# Sheet1.net
KiCad netlist of a schematic drawn in Altium Designer
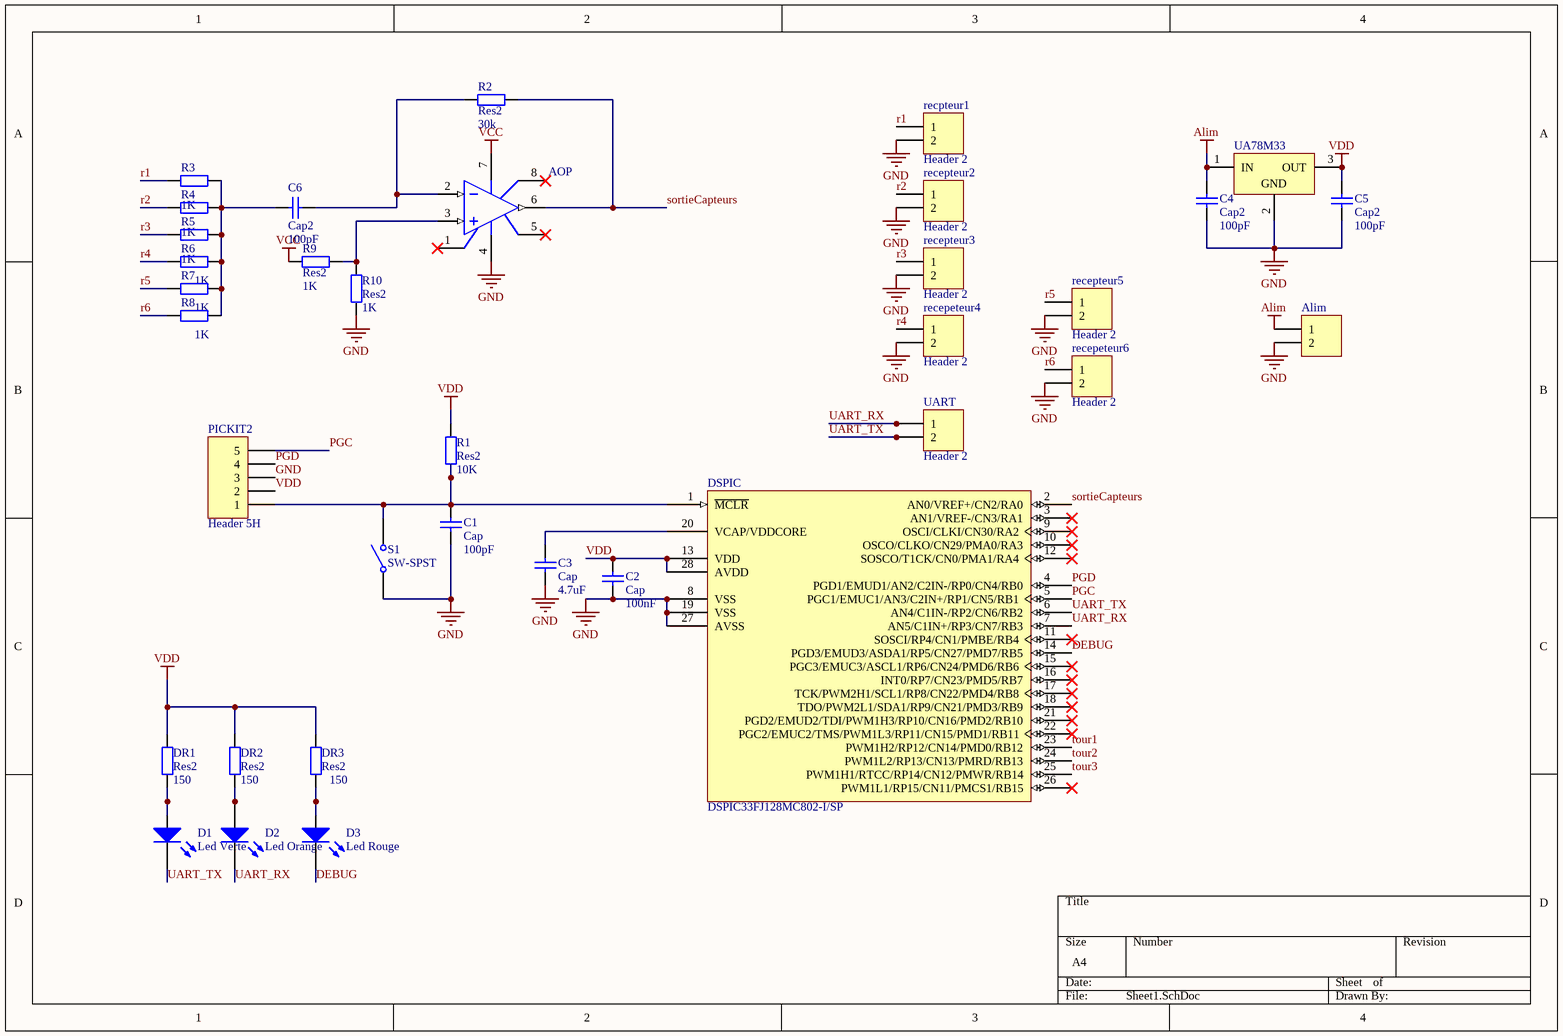
[diagram p0: Sheet1.SchDoc]

(export (version "E")
  (design (tool "Eeschema 10.0.6"))
  (components
    (comp (ref "Alim")
      (value "Header 2")
      (footprint "HDR1X2")
      (description "Header, 2-Pin")
      (fields (field (name "PUBLISHER") "Altium Limited"))
      (libsource (lib "Miscellaneous Connectors") (part "Header 2"))
    )
    (comp (ref "AOP")
      (value "TL081CN")
      (footprint "DIP8")
      (description "General-Purpose J-FET Single Operational Amplifier")
      (fields (field (name "PUBLISHER") "Altium Limited"))
      (libsource (lib "LIBRAIRIE_INTEGREE_PHELMA1") (part "TL081CN"))
    )
    (comp (ref "C1")
      (value "Cap")
      (footprint "RAD-0.3")
      (description "Capacitor")
      (fields (field (name "ALTIUM_VALUE") "100pF") (field (name "PUBLISHER") "Altium Limited"))
      (libsource (lib "Miscellaneous Devices") (part "Cap"))
    )
    (comp (ref "C2")
      (value "Cap")
      (footprint "RAD-0.3")
      (description "Capacitor")
      (fields (field (name "ALTIUM_VALUE") "100nF") (field (name "PUBLISHER") "Altium Limited"))
      (libsource (lib "Miscellaneous Devices") (part "Cap"))
    )
    (comp (ref "C3")
      (value "Cap")
      (footprint "RAD-0.3")
      (description "Capacitor")
      (fields (field (name "ALTIUM_VALUE") "4.7uF") (field (name "PUBLISHER") "Altium Limited"))
      (libsource (lib "Miscellaneous Devices") (part "Cap"))
    )
    (comp (ref "C4")
      (value "Cap2")
      (footprint "CAPA2")
      (description "Capacitor")
      (fields (field (name "ALTIUM_VALUE") "100pF") (field (name "PUBLISHER") "Altium Limited"))
      (libsource (lib "LIBRAIRIE_INTEGREE_PHELMA1") (part "Cap2"))
    )
    (comp (ref "C5")
      (value "Cap2")
      (footprint "CAPA2")
      (description "Capacitor")
      (fields (field (name "ALTIUM_VALUE") "100pF") (field (name "PUBLISHER") "Altium Limited"))
      (libsource (lib "LIBRAIRIE_INTEGREE_PHELMA1") (part "Cap2"))
    )
    (comp (ref "C6")
      (value "Cap2")
      (footprint "CAPA2")
      (description "Capacitor")
      (fields (field (name "ALTIUM_VALUE") "100pF") (field (name "PUBLISHER") "Altium Limited"))
      (libsource (lib "LIBRAIRIE_INTEGREE_PHELMA1") (part "Cap2"))
    )
    (comp (ref "D1")
      (value "Led Verte")
      (footprint "LED")
      (description "LED")
      (fields (field (name "PUBLISHER") "Altium Limited"))
      (libsource (lib "LIBRAIRIE_INTEGREE_PHELMA1") (part "Led"))
    )
    (comp (ref "D2")
      (value "Led Orange")
      (footprint "LED")
      (description "LED")
      (fields (field (name "PUBLISHER") "Altium Limited"))
      (libsource (lib "LIBRAIRIE_INTEGREE_PHELMA1") (part "Led"))
    )
    (comp (ref "D3")
      (value "Led Rouge")
      (footprint "LED")
      (description "LED")
      (fields (field (name "PUBLISHER") "Altium Limited"))
      (libsource (lib "LIBRAIRIE_INTEGREE_PHELMA1") (part "Led"))
    )
    (comp (ref "DR1")
      (value "Res2")
      (footprint "AXIAL-0.4")
      (description "Resistor")
      (fields (field (name "ALTIUM_VALUE") "150") (field (name "PUBLISHER") "Altium Limited"))
      (libsource (lib "Miscellaneous Devices") (part "Res2"))
    )
    (comp (ref "DR2")
      (value "Res2")
      (footprint "AXIAL-0.4")
      (description "Resistor")
      (fields (field (name "ALTIUM_VALUE") "150") (field (name "PUBLISHER") "Altium Limited"))
      (libsource (lib "Miscellaneous Devices") (part "Res2"))
    )
    (comp (ref "DR3")
      (value "Res2")
      (footprint "AXIAL-0.4")
      (description "Resistor")
      (fields (field (name "ALTIUM_VALUE") "150") (field (name "PUBLISHER") "Altium Limited"))
      (libsource (lib "Miscellaneous Devices") (part "Res2"))
    )
    (comp (ref "DSPIC")
      (value "DSPIC33FJ128MC802-I/SP")
      (footprint "SPDIP300-SP28")
      (fields (field (name "PUBLISHER") "Altium Limited"))
      (libsource (lib "Microchip DSC 16-Bit dsPIC33F") (part "DSPIC33FJ128MC802-I/SP"))
    )
    (comp (ref "PICKIT2")
      (value "Header 5H")
      (footprint "HDR1X5")
      (description "Header, 5-Pin, Right Angle")
      (fields (field (name "PUBLISHER") "Altium Limited"))
      (libsource (lib "Miscellaneous Connectors") (part "Header 5H"))
    )
    (comp (ref "R1")
      (value "Res2")
      (footprint "AXIAL-0.4")
      (description "Resistor")
      (fields (field (name "ALTIUM_VALUE") "10K") (field (name "PUBLISHER") "Altium Limited"))
      (libsource (lib "Miscellaneous Devices") (part "Res2"))
    )
    (comp (ref "R2")
      (value "Res2")
      (footprint "res5_1/4W")
      (description "Resistor")
      (fields (field (name "ALTIUM_VALUE") "30k") (field (name "PUBLISHER") "Altium Limited"))
      (libsource (lib "LIBRAIRIE_INTEGREE_PHELMA1") (part "Res2"))
    )
    (comp (ref "R3")
      (value "1K")
      (footprint "res5_1/4W")
      (description "Resistor")
      (fields (field (name "Comment") "Res2") (field (name "PUBLISHER") "Altium Limited"))
      (libsource (lib "LIBRAIRIE_INTEGREE_PHELMA1") (part "Res2"))
    )
    (comp (ref "R4")
      (value "1K")
      (footprint "res5_1/4W")
      (description "Resistor")
      (fields (field (name "Comment") "Res2") (field (name "PUBLISHER") "Altium Limited"))
      (libsource (lib "LIBRAIRIE_INTEGREE_PHELMA1") (part "Res2"))
    )
    (comp (ref "R5")
      (value "1K")
      (footprint "res5_1/4W")
      (description "Resistor")
      (fields (field (name "Comment") "Res2") (field (name "PUBLISHER") "Altium Limited"))
      (libsource (lib "LIBRAIRIE_INTEGREE_PHELMA1") (part "Res2"))
    )
    (comp (ref "R6")
      (value "1K")
      (footprint "res5_1/4W")
      (description "Resistor")
      (fields (field (name "Comment") "Res2") (field (name "PUBLISHER") "Altium Limited"))
      (libsource (lib "LIBRAIRIE_INTEGREE_PHELMA1") (part "Res2"))
    )
    (comp (ref "R7")
      (value "1K")
      (footprint "res5_1/4W")
      (description "Resistor")
      (fields (field (name "Comment") "Res2") (field (name "PUBLISHER") "Altium Limited"))
      (libsource (lib "LIBRAIRIE_INTEGREE_PHELMA1") (part "Res2"))
    )
    (comp (ref "R8")
      (value "1K")
      (footprint "res5_1/4W")
      (description "Resistor")
      (fields (field (name "Comment") "Res2") (field (name "PUBLISHER") "Altium Limited"))
      (libsource (lib "LIBRAIRIE_INTEGREE_PHELMA1") (part "Res2"))
    )
    (comp (ref "R9")
      (value "Res2")
      (footprint "res5_1/4W")
      (description "Resistor")
      (fields (field (name "ALTIUM_VALUE") "1K") (field (name "PUBLISHER") "Altium Limited"))
      (libsource (lib "LIBRAIRIE_INTEGREE_PHELMA1") (part "Res2"))
    )
    (comp (ref "R10")
      (value "Res2")
      (footprint "res5_1/4W")
      (description "Resistor")
      (fields (field (name "ALTIUM_VALUE") "1K") (field (name "PUBLISHER") "Altium Limited"))
      (libsource (lib "") (part "Res2_1"))
    )
    (comp (ref "recepeteur4")
      (value "Header 2")
      (footprint "HDR1X2")
      (description "Header, 2-Pin")
      (fields (field (name "PUBLISHER") "Altium Limited"))
      (libsource (lib "Miscellaneous Connectors") (part "Header 2"))
    )
    (comp (ref "recepeteur6")
      (value "Header 2")
      (footprint "HDR1X2")
      (description "Header, 2-Pin")
      (fields (field (name "PUBLISHER") "Altium Limited"))
      (libsource (lib "Miscellaneous Connectors") (part "Header 2"))
    )
    (comp (ref "recepteur2")
      (value "Header 2")
      (footprint "HDR1X2")
      (description "Header, 2-Pin")
      (fields (field (name "PUBLISHER") "Altium Limited"))
      (libsource (lib "Miscellaneous Connectors") (part "Header 2"))
    )
    (comp (ref "recepteur3")
      (value "Header 2")
      (footprint "HDR1X2")
      (description "Header, 2-Pin")
      (fields (field (name "PUBLISHER") "Altium Limited"))
      (libsource (lib "Miscellaneous Connectors") (part "Header 2"))
    )
    (comp (ref "recepteur5")
      (value "Header 2")
      (footprint "HDR1X2")
      (description "Header, 2-Pin")
      (fields (field (name "PUBLISHER") "Altium Limited"))
      (libsource (lib "Miscellaneous Connectors") (part "Header 2"))
    )
    (comp (ref "recpteur1")
      (value "Header 2")
      (footprint "HDR1X2")
      (description "Header, 2-Pin")
      (fields (field (name "PUBLISHER") "Altium Limited"))
      (libsource (lib "Miscellaneous Connectors") (part "Header 2"))
    )
    (comp (ref "S1")
      (value "SW-SPST")
      (footprint "SPST-2")
      (description "Single-Pole, Single-Throw Switch")
      (fields (field (name "PUBLISHER") "Altium Limited"))
      (libsource (lib "Miscellaneous Devices") (part "SW-SPST"))
    )
    (comp (ref "UA78M33")
      (value "LM7805CT")
      (footprint "TO220")
      (description "Series 3-Terminal Positive Regulator")
      (fields (field (name "PUBLISHER") "Altium Limited"))
      (libsource (lib "LIBRAIRIE_INTEGREE_PHELMA1") (part "LM7805CT"))
    )
    (comp (ref "UART")
      (value "Header 2")
      (footprint "HDR1X2")
      (description "Header, 2-Pin")
      (fields (field (name "PUBLISHER") "Altium Limited"))
      (libsource (lib "Miscellaneous Connectors") (part "Header 2"))
    )
  )
  (nets
    (net (code "1") (name "/DEBUG") (class "Default")
      (node (ref "D3") (pin "2") (pinfunction "K_2") (pintype "passive"))
      (node (ref "DSPIC") (pin "14") (pinfunction "PGD3/EMUD3/ASDA1/RP5/CN27/PMD7/RB5_14") (pintype "bidirectional"))
    )
    (net (code "2") (name "/PGC") (class "Default")
      (node (ref "DSPIC") (pin "5") (pinfunction "PGC1/EMUC1/AN3/C2IN+/RP1/CN5/RB1_5") (pintype "bidirectional"))
      (node (ref "PICKIT2") (pin "5") (pinfunction "5_5") (pintype "passive"))
    )
    (net (code "3") (name "/PGD") (class "Default")
      (node (ref "DSPIC") (pin "4") (pinfunction "PGD1/EMUD1/AN2/C2IN-/RP0/CN4/RB0_4") (pintype "bidirectional"))
      (node (ref "PICKIT2") (pin "4") (pinfunction "4_4") (pintype "passive"))
    )
    (net (code "4") (name "/UART_RX") (class "Default")
      (node (ref "D2") (pin "2") (pinfunction "K_2") (pintype "passive"))
      (node (ref "DSPIC") (pin "7") (pinfunction "AN5/C1IN+/RP3/CN7/RB3_7") (pintype "bidirectional"))
      (node (ref "UART") (pin "1") (pinfunction "1_1") (pintype "passive"))
    )
    (net (code "5") (name "/UART_TX") (class "Default")
      (node (ref "D1") (pin "2") (pinfunction "K_2") (pintype "passive"))
      (node (ref "DSPIC") (pin "6") (pinfunction "AN4/C1IN-/RP2/CN6/RB2_6") (pintype "bidirectional"))
      (node (ref "UART") (pin "2") (pinfunction "2_2") (pintype "passive"))
    )
    (net (code "6") (name "/r1") (class "Default")
      (node (ref "R3") (pin "1") (pinfunction "1_1") (pintype "passive"))
      (node (ref "recpteur1") (pin "1") (pinfunction "1_1") (pintype "passive"))
    )
    (net (code "7") (name "/r2") (class "Default")
      (node (ref "R4") (pin "1") (pinfunction "1_1") (pintype "passive"))
      (node (ref "recepteur2") (pin "1") (pinfunction "1_1") (pintype "passive"))
    )
    (net (code "8") (name "/r3") (class "Default")
      (node (ref "R5") (pin "1") (pinfunction "1_1") (pintype "passive"))
      (node (ref "recepteur3") (pin "1") (pinfunction "1_1") (pintype "passive"))
    )
    (net (code "9") (name "/r4") (class "Default")
      (node (ref "R6") (pin "1") (pinfunction "1_1") (pintype "passive"))
      (node (ref "recepeteur4") (pin "1") (pinfunction "1_1") (pintype "passive"))
    )
    (net (code "10") (name "/r5") (class "Default")
      (node (ref "R7") (pin "1") (pinfunction "1_1") (pintype "passive"))
      (node (ref "recepteur5") (pin "1") (pinfunction "1_1") (pintype "passive"))
    )
    (net (code "11") (name "/r6") (class "Default")
      (node (ref "R8") (pin "1") (pinfunction "1_1") (pintype "passive"))
      (node (ref "recepeteur6") (pin "1") (pinfunction "1_1") (pintype "passive"))
    )
    (net (code "12") (name "/sortieCapteurs") (class "Default")
      (node (ref "AOP") (pin "6") (pinfunction "OUT_6") (pintype "output"))
      (node (ref "DSPIC") (pin "2") (pinfunction "AN0/VREF+/CN2/RA0_2") (pintype "bidirectional"))
      (node (ref "R2") (pin "2") (pinfunction "2_2") (pintype "passive"))
    )
    (net (code "13") (name "/tour1") (class "Default")
      (node (ref "DSPIC") (pin "23") (pinfunction "PWM1H2/RP12/CN14/PMD0/RB12_23") (pintype "bidirectional"))
    )
    (net (code "14") (name "/tour2") (class "Default")
      (node (ref "DSPIC") (pin "24") (pinfunction "PWM1L2/RP13/CN13/PMRD/RB13_24") (pintype "bidirectional"))
    )
    (net (code "15") (name "/tour3") (class "Default")
      (node (ref "DSPIC") (pin "25") (pinfunction "PWM1H1/RTCC/RP14/CN12/PMWR/RB14_25") (pintype "bidirectional"))
    )
    (net (code "16") (name "Alim") (class "Default")
      (node (ref "Alim") (pin "1") (pinfunction "1_1") (pintype "passive"))
      (node (ref "C4") (pin "2") (pinfunction "2_2") (pintype "passive"))
      (node (ref "UA78M33") (pin "1") (pinfunction "IN_1") (pintype "power_in"))
    )
    (net (code "17") (name "GND") (class "Default")
      (node (ref "AOP") (pin "4") (pinfunction "V-_4") (pintype "power_in"))
      (node (ref "Alim") (pin "2") (pinfunction "2_2") (pintype "passive"))
      (node (ref "C1") (pin "1") (pinfunction "1_1") (pintype "passive"))
      (node (ref "C2") (pin "1") (pinfunction "1_1") (pintype "passive"))
      (node (ref "C3") (pin "1") (pinfunction "1_1") (pintype "passive"))
      (node (ref "C4") (pin "1") (pinfunction "1_1") (pintype "passive"))
      (node (ref "C5") (pin "1") (pinfunction "1_1") (pintype "passive"))
      (node (ref "DSPIC") (pin "19") (pinfunction "VSS_19") (pintype "power_in"))
      (node (ref "DSPIC") (pin "27") (pinfunction "AVSS_27") (pintype "power_in"))
      (node (ref "DSPIC") (pin "8") (pinfunction "VSS_8") (pintype "power_in"))
      (node (ref "PICKIT2") (pin "3") (pinfunction "3_3") (pintype "passive"))
      (node (ref "R10") (pin "1") (pinfunction "1_1") (pintype "passive"))
      (node (ref "S1") (pin "1") (pinfunction "COMMON_1") (pintype "passive"))
      (node (ref "UA78M33") (pin "2") (pinfunction "GND_2") (pintype "power_in"))
      (node (ref "recepeteur4") (pin "2") (pinfunction "2_2") (pintype "passive"))
      (node (ref "recepeteur6") (pin "2") (pinfunction "2_2") (pintype "passive"))
      (node (ref "recepteur2") (pin "2") (pinfunction "2_2") (pintype "passive"))
      (node (ref "recepteur3") (pin "2") (pinfunction "2_2") (pintype "passive"))
      (node (ref "recepteur5") (pin "2") (pinfunction "2_2") (pintype "passive"))
      (node (ref "recpteur1") (pin "2") (pinfunction "2_2") (pintype "passive"))
    )
    (net (code "18") (name "Net-(AOP-IN+)") (class "Default")
      (node (ref "AOP") (pin "3") (pinfunction "IN+_3") (pintype "input"))
      (node (ref "R10") (pin "2") (pinfunction "2_2") (pintype "passive"))
      (node (ref "R9") (pin "2") (pinfunction "2_2") (pintype "passive"))
    )
    (net (code "19") (name "Net-(AOP-IN-)") (class "Default")
      (node (ref "AOP") (pin "2") (pinfunction "IN-_2") (pintype "input"))
      (node (ref "C6") (pin "2") (pinfunction "2_2") (pintype "passive"))
      (node (ref "R2") (pin "1") (pinfunction "1_1") (pintype "passive"))
    )
    (net (code "20") (name "Net-(C6-Pad1)") (class "Default")
      (node (ref "C6") (pin "1") (pinfunction "1_1") (pintype "passive"))
      (node (ref "R3") (pin "2") (pinfunction "2_2") (pintype "passive"))
      (node (ref "R4") (pin "2") (pinfunction "2_2") (pintype "passive"))
      (node (ref "R5") (pin "2") (pinfunction "2_2") (pintype "passive"))
      (node (ref "R6") (pin "2") (pinfunction "2_2") (pintype "passive"))
      (node (ref "R7") (pin "2") (pinfunction "2_2") (pintype "passive"))
      (node (ref "R8") (pin "2") (pinfunction "2_2") (pintype "passive"))
    )
    (net (code "21") (name "Net-(D1-A)") (class "Default")
      (node (ref "D1") (pin "1") (pinfunction "A_1") (pintype "passive"))
      (node (ref "DR1") (pin "1") (pinfunction "1_1") (pintype "passive"))
    )
    (net (code "22") (name "Net-(D2-A)") (class "Default")
      (node (ref "D2") (pin "1") (pinfunction "A_1") (pintype "passive"))
      (node (ref "DR2") (pin "1") (pinfunction "1_1") (pintype "passive"))
    )
    (net (code "23") (name "Net-(D3-A)") (class "Default")
      (node (ref "D3") (pin "1") (pinfunction "A_1") (pintype "passive"))
      (node (ref "DR3") (pin "1") (pinfunction "1_1") (pintype "passive"))
    )
    (net (code "24") (name "Net-(DSPIC-VCAP{slash}VDDCORE)") (class "Default")
      (node (ref "C3") (pin "2") (pinfunction "2_2") (pintype "passive"))
      (node (ref "DSPIC") (pin "20") (pinfunction "VCAP/VDDCORE_20") (pintype "power_in"))
    )
    (net (code "25") (name "Net-(DSPIC-~{MCLR})") (class "Default")
      (node (ref "C1") (pin "2") (pinfunction "2_2") (pintype "passive"))
      (node (ref "DSPIC") (pin "1") (pinfunction "~{MCLR}_1") (pintype "input"))
      (node (ref "PICKIT2") (pin "1") (pinfunction "1_1") (pintype "passive"))
      (node (ref "R1") (pin "1") (pinfunction "1_1") (pintype "passive"))
      (node (ref "S1") (pin "2") (pinfunction "NO_2") (pintype "passive"))
    )
    (net (code "26") (name "VCC") (class "Default")
      (node (ref "AOP") (pin "7") (pinfunction "V+_7") (pintype "power_in"))
      (node (ref "R9") (pin "1") (pinfunction "1_1") (pintype "passive"))
    )
    (net (code "27") (name "VDD") (class "Default")
      (node (ref "C2") (pin "2") (pinfunction "2_2") (pintype "passive"))
      (node (ref "C5") (pin "2") (pinfunction "2_2") (pintype "passive"))
      (node (ref "DR1") (pin "2") (pinfunction "2_2") (pintype "passive"))
      (node (ref "DR2") (pin "2") (pinfunction "2_2") (pintype "passive"))
      (node (ref "DR3") (pin "2") (pinfunction "2_2") (pintype "passive"))
      (node (ref "DSPIC") (pin "13") (pinfunction "VDD_13") (pintype "power_in"))
      (node (ref "DSPIC") (pin "28") (pinfunction "AVDD_28") (pintype "power_in"))
      (node (ref "PICKIT2") (pin "2") (pinfunction "2_2") (pintype "passive"))
      (node (ref "R1") (pin "2") (pinfunction "2_2") (pintype "passive"))
      (node (ref "UA78M33") (pin "3") (pinfunction "OUT_3") (pintype "power_in"))
    )
    (net (code "28") (name "unconnected-(AOP-NC-Pad8)") (class "Default")
      (node (ref "AOP") (pin "8") (pinfunction "NC_8") (pintype "passive+no_connect"))
    )
    (net (code "29") (name "unconnected-(AOP-OS_NULL-Pad1)") (class "Default")
      (node (ref "AOP") (pin "1") (pinfunction "OS_NULL_1") (pintype "passive+no_connect"))
    )
    (net (code "30") (name "unconnected-(AOP-OS_NULL-Pad5)") (class "Default")
      (node (ref "AOP") (pin "5") (pinfunction "OS_NULL_5") (pintype "passive+no_connect"))
    )
    (net (code "31") (name "unconnected-(DSPIC-AN1{slash}VREF-{slash}CN3{slash}RA1-Pad3)") (class "Default")
      (node (ref "DSPIC") (pin "3") (pinfunction "AN1/VREF-/CN3/RA1_3") (pintype "bidirectional+no_connect"))
    )
    (net (code "32") (name "unconnected-(DSPIC-INT0{slash}RP7{slash}CN23{slash}PMD5{slash}RB7-Pad16)") (class "Default")
      (node (ref "DSPIC") (pin "16") (pinfunction "INT0/RP7/CN23/PMD5/RB7_16") (pintype "bidirectional+no_connect"))
    )
    (net (code "33") (name "unconnected-(DSPIC-OSCI{slash}CLKI{slash}CN30{slash}RA2-Pad9)") (class "Default")
      (node (ref "DSPIC") (pin "9") (pinfunction "OSCI/CLKI/CN30/RA2_9") (pintype "bidirectional+no_connect"))
    )
    (net (code "34") (name "unconnected-(DSPIC-OSCO{slash}CLKO{slash}CN29{slash}PMA0{slash}RA3-Pad10)") (class "Default")
      (node (ref "DSPIC") (pin "10") (pinfunction "OSCO/CLKO/CN29/PMA0/RA3_10") (pintype "bidirectional+no_connect"))
    )
    (net (code "35") (name "unconnected-(DSPIC-PGC2{slash}EMUC2{slash}TMS{slash}PWM1L3{slash}RP11{slash}CN15{slash}PMD1{slash}RB11-Pad22)") (class "Default")
      (node (ref "DSPIC") (pin "22") (pinfunction "PGC2/EMUC2/TMS/PWM1L3/RP11/CN15/PMD1/RB11_22") (pintype "bidirectional+no_connect"))
    )
    (net (code "36") (name "unconnected-(DSPIC-PGC3{slash}EMUC3{slash}ASCL1{slash}RP6{slash}CN24{slash}PMD6{slash}RB6-Pad15)") (class "Default")
      (node (ref "DSPIC") (pin "15") (pinfunction "PGC3/EMUC3/ASCL1/RP6/CN24/PMD6/RB6_15") (pintype "bidirectional+no_connect"))
    )
    (net (code "37") (name "unconnected-(DSPIC-PGD2{slash}EMUD2{slash}TDI{slash}PWM1H3{slash}RP10{slash}CN16{slash}PMD2{slash}RB10-Pad21)") (class "Default")
      (node (ref "DSPIC") (pin "21") (pinfunction "PGD2/EMUD2/TDI/PWM1H3/RP10/CN16/PMD2/RB10_21") (pintype "bidirectional+no_connect"))
    )
    (net (code "38") (name "unconnected-(DSPIC-PWM1L1{slash}RP15{slash}CN11{slash}PMCS1{slash}RB15-Pad26)") (class "Default")
      (node (ref "DSPIC") (pin "26") (pinfunction "PWM1L1/RP15/CN11/PMCS1/RB15_26") (pintype "bidirectional+no_connect"))
    )
    (net (code "39") (name "unconnected-(DSPIC-SOSCI{slash}RP4{slash}CN1{slash}PMBE{slash}RB4-Pad11)") (class "Default")
      (node (ref "DSPIC") (pin "11") (pinfunction "SOSCI/RP4/CN1/PMBE/RB4_11") (pintype "bidirectional+no_connect"))
    )
    (net (code "40") (name "unconnected-(DSPIC-SOSCO{slash}T1CK{slash}CN0{slash}PMA1{slash}RA4-Pad12)") (class "Default")
      (node (ref "DSPIC") (pin "12") (pinfunction "SOSCO/T1CK/CN0/PMA1/RA4_12") (pintype "bidirectional+no_connect"))
    )
    (net (code "41") (name "unconnected-(DSPIC-TCK{slash}PWM2H1{slash}SCL1{slash}RP8{slash}CN22{slash}PMD4{slash}RB8-Pad17)") (class "Default")
      (node (ref "DSPIC") (pin "17") (pinfunction "TCK/PWM2H1/SCL1/RP8/CN22/PMD4/RB8_17") (pintype "bidirectional+no_connect"))
    )
    (net (code "42") (name "unconnected-(DSPIC-TDO{slash}PWM2L1{slash}SDA1{slash}RP9{slash}CN21{slash}PMD3{slash}RB9-Pad18)") (class "Default")
      (node (ref "DSPIC") (pin "18") (pinfunction "TDO/PWM2L1/SDA1/RP9/CN21/PMD3/RB9_18") (pintype "bidirectional+no_connect"))
    )
  )
)
